# Boost.net
KiCad netlist of a schematic drawn in EAGLE
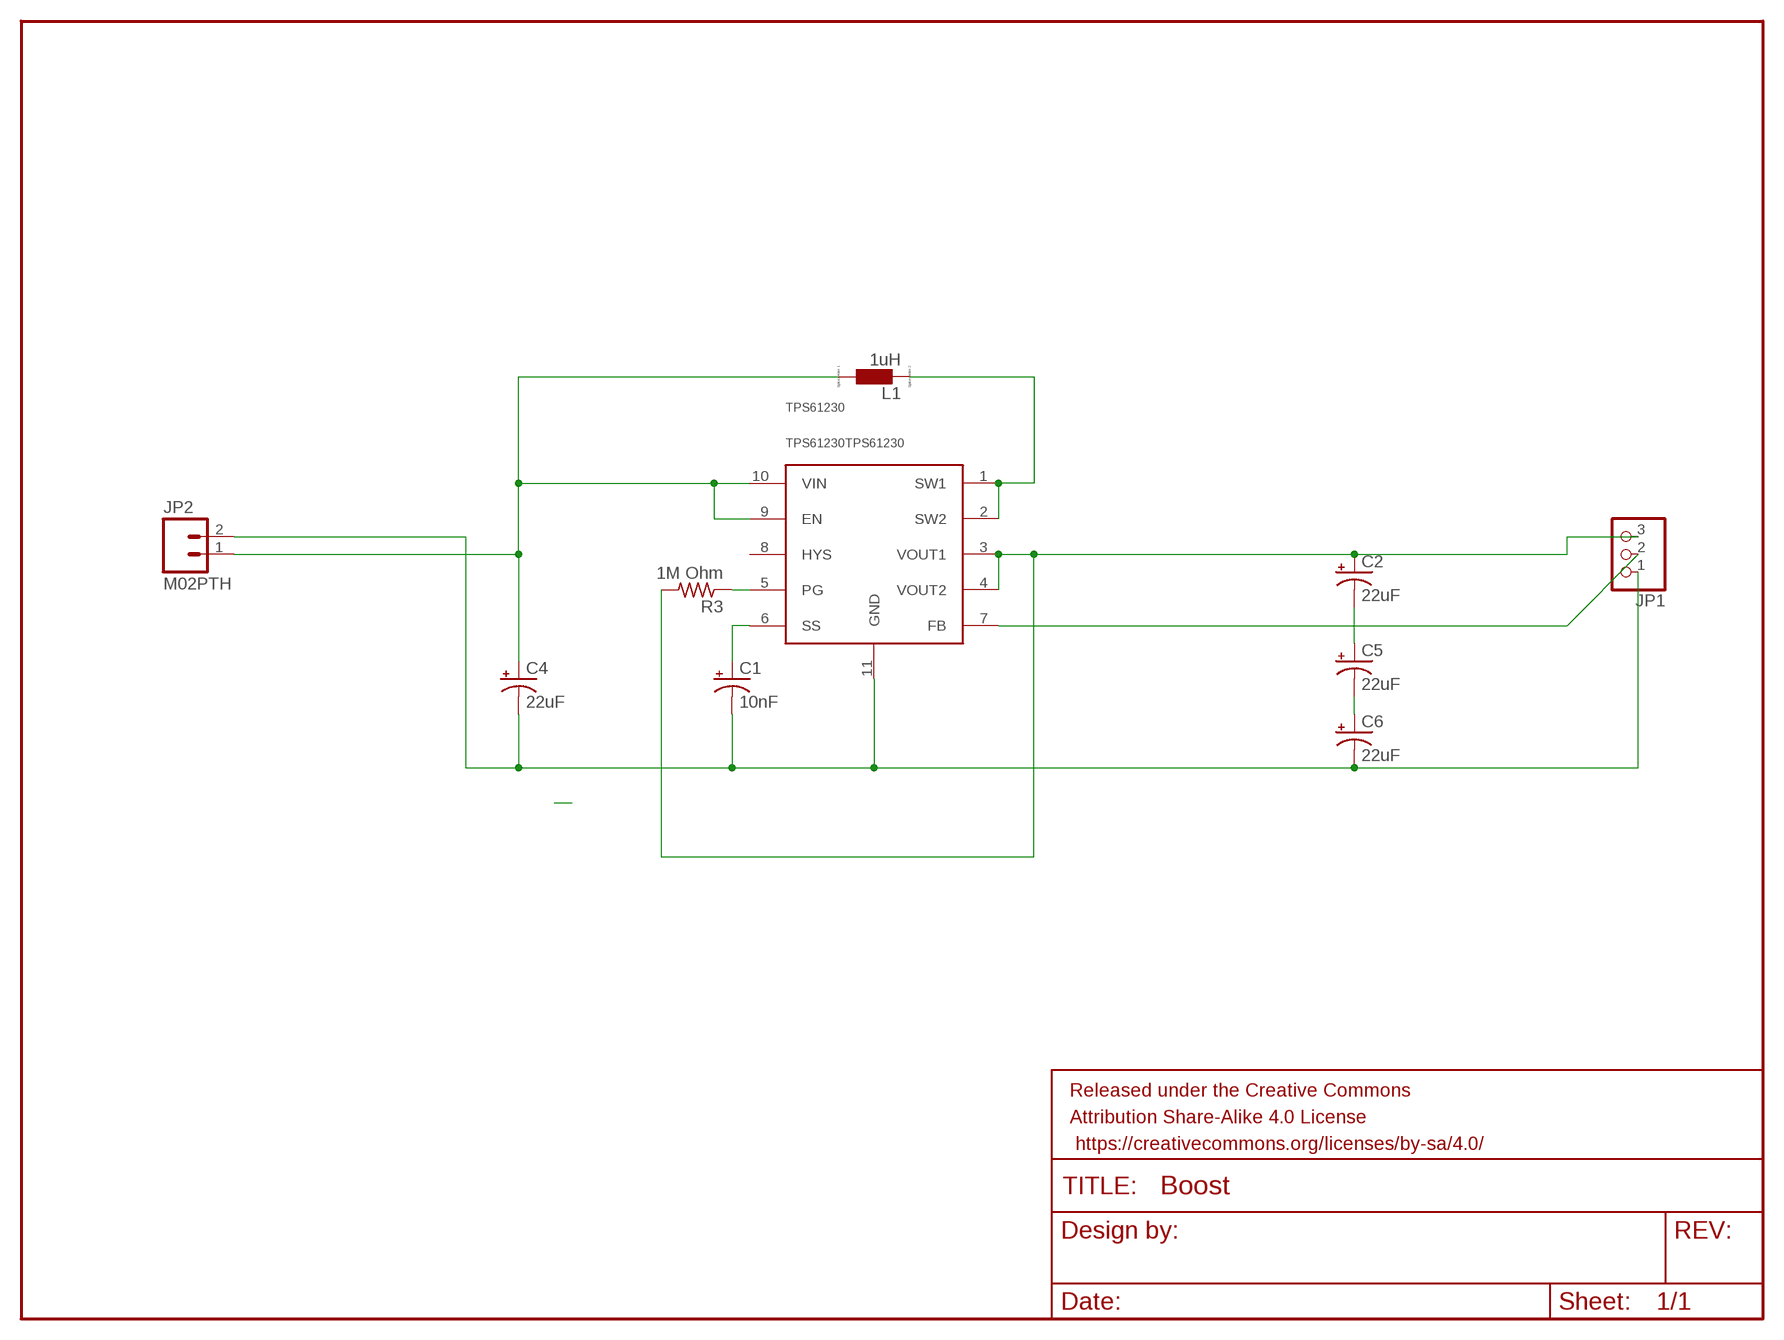
[diagram p0: schematic, sheet 1]

(export (version "E")
  (design (tool "Eeschema 10.0.6"))
  (components
    (comp (ref "C1")
      (value "10nF")
      (footprint "eagle-import:E2,5-5")
      (libsource (lib "eagle-import") (part "CPOL-USE2.5-5"))
    )
    (comp (ref "C2")
      (value "22uF")
      (footprint "eagle-import:E2,5-5")
      (libsource (lib "eagle-import") (part "CPOL-USE2.5-5"))
    )
    (comp (ref "C4")
      (value "22uF")
      (footprint "eagle-import:E2,5-5")
      (libsource (lib "eagle-import") (part "CPOL-USE2.5-5"))
    )
    (comp (ref "C5")
      (value "22uF")
      (footprint "eagle-import:E2,5-5")
      (libsource (lib "eagle-import") (part "CPOL-USE2.5-5"))
    )
    (comp (ref "C6")
      (value "22uF")
      (footprint "eagle-import:E2,5-5")
      (libsource (lib "eagle-import") (part "CPOL-USE2.5-5"))
    )
    (comp (ref "FRAME1")
      (value "FRAME-LETTER")
      (footprint "eagle-import:CREATIVE_COMMONS")
      (libsource (lib "eagle-import") (part "FRAME-LETTER"))
    )
    (comp (ref "JP1")
      (value "PINHD-1X3")
      (footprint "eagle-import:1X03")
      (libsource (lib "eagle-import") (part "PINHD-1X3"))
    )
    (comp (ref "JP2")
      (value "M02PTH")
      (footprint "eagle-import:1X02")
      (libsource (lib "eagle-import") (part "M02PTH"))
    )
    (comp (ref "L1")
      (value "1uH")
      (footprint "eagle-import:0207_10")
      (libsource (lib "eagle-import") (part "L0207/10"))
    )
    (comp (ref "R3")
      (value "1M Ohm")
      (footprint "eagle-import:0207_10")
      (libsource (lib "eagle-import") (part "R-US_0207/10"))
    )
    (comp (ref "TPS61230")
      (value "TPS61230TPS61230")
      (footprint "eagle-import:SON50P300X300X100-11N")
      (libsource (lib "eagle-import") (part "TPS61230TPS61230"))
    )
  )
  (nets
    (net (code "1") (name "Net-(C2-Pad-)") (class "Default")
      (node (ref "C2") (pin "-") (pinfunction "-_-") (pintype "passive"))
      (node (ref "C5") (pin "+") (pinfunction "+_+") (pintype "passive"))
    )
    (net (code "2") (name "Net-(C5-Pad-)") (class "Default")
      (node (ref "C5") (pin "-") (pinfunction "-_-") (pintype "passive"))
      (node (ref "C6") (pin "+") (pinfunction "+_+") (pintype "passive"))
    )
    (net (code "3") (name "Net-(TPS61230-EN)") (class "Default")
      (node (ref "C4") (pin "+") (pinfunction "+_+") (pintype "passive"))
      (node (ref "JP2") (pin "1") (pinfunction "1_1") (pintype "passive"))
      (node (ref "L1") (pin "1") (pinfunction "1_1") (pintype "passive"))
      (node (ref "TPS61230") (pin "10") (pinfunction "VIN_10") (pintype "bidirectional"))
      (node (ref "TPS61230") (pin "9") (pinfunction "EN_9") (pintype "bidirectional"))
    )
    (net (code "4") (name "Net-(TPS61230-FB)") (class "Default")
      (node (ref "JP1") (pin "2") (pinfunction "2_2") (pintype "passive"))
      (node (ref "TPS61230") (pin "7") (pinfunction "FB_7") (pintype "bidirectional"))
    )
    (net (code "5") (name "Net-(TPS61230-GND)") (class "Default")
      (node (ref "C1") (pin "-") (pinfunction "-_-") (pintype "passive"))
      (node (ref "C4") (pin "-") (pinfunction "-_-") (pintype "passive"))
      (node (ref "C6") (pin "-") (pinfunction "-_-") (pintype "passive"))
      (node (ref "JP1") (pin "1") (pinfunction "1_1") (pintype "passive"))
      (node (ref "JP2") (pin "2") (pinfunction "2_2") (pintype "passive"))
      (node (ref "TPS61230") (pin "11") (pinfunction "GND_11") (pintype "bidirectional"))
    )
    (net (code "6") (name "Net-(TPS61230-PG)") (class "Default")
      (node (ref "R3") (pin "1") (pinfunction "1_1") (pintype "passive"))
      (node (ref "TPS61230") (pin "5") (pinfunction "PG_5") (pintype "bidirectional"))
    )
    (net (code "7") (name "Net-(TPS61230-SS)") (class "Default")
      (node (ref "C1") (pin "+") (pinfunction "+_+") (pintype "passive"))
      (node (ref "TPS61230") (pin "6") (pinfunction "SS_6") (pintype "bidirectional"))
    )
    (net (code "8") (name "Net-(TPS61230-SW1)") (class "Default")
      (node (ref "L1") (pin "2") (pinfunction "2_2") (pintype "passive"))
      (node (ref "TPS61230") (pin "1") (pinfunction "SW1_1") (pintype "bidirectional"))
      (node (ref "TPS61230") (pin "2") (pinfunction "SW2_2") (pintype "bidirectional"))
    )
    (net (code "9") (name "Net-(TPS61230-VOUT1)") (class "Default")
      (node (ref "C2") (pin "+") (pinfunction "+_+") (pintype "passive"))
      (node (ref "JP1") (pin "3") (pinfunction "3_3") (pintype "passive"))
      (node (ref "R3") (pin "2") (pinfunction "2_2") (pintype "passive"))
      (node (ref "TPS61230") (pin "3") (pinfunction "VOUT1_3") (pintype "bidirectional"))
      (node (ref "TPS61230") (pin "4") (pinfunction "VOUT2_4") (pintype "bidirectional"))
    )
    (net (code "10") (name "unconnected-(TPS61230-HYS-Pad8)") (class "Default")
      (node (ref "TPS61230") (pin "8") (pinfunction "HYS_8") (pintype "bidirectional"))
    )
  )
)
